# flow3r-pot.net
KiCad netlist of a schematic drawn in EAGLE
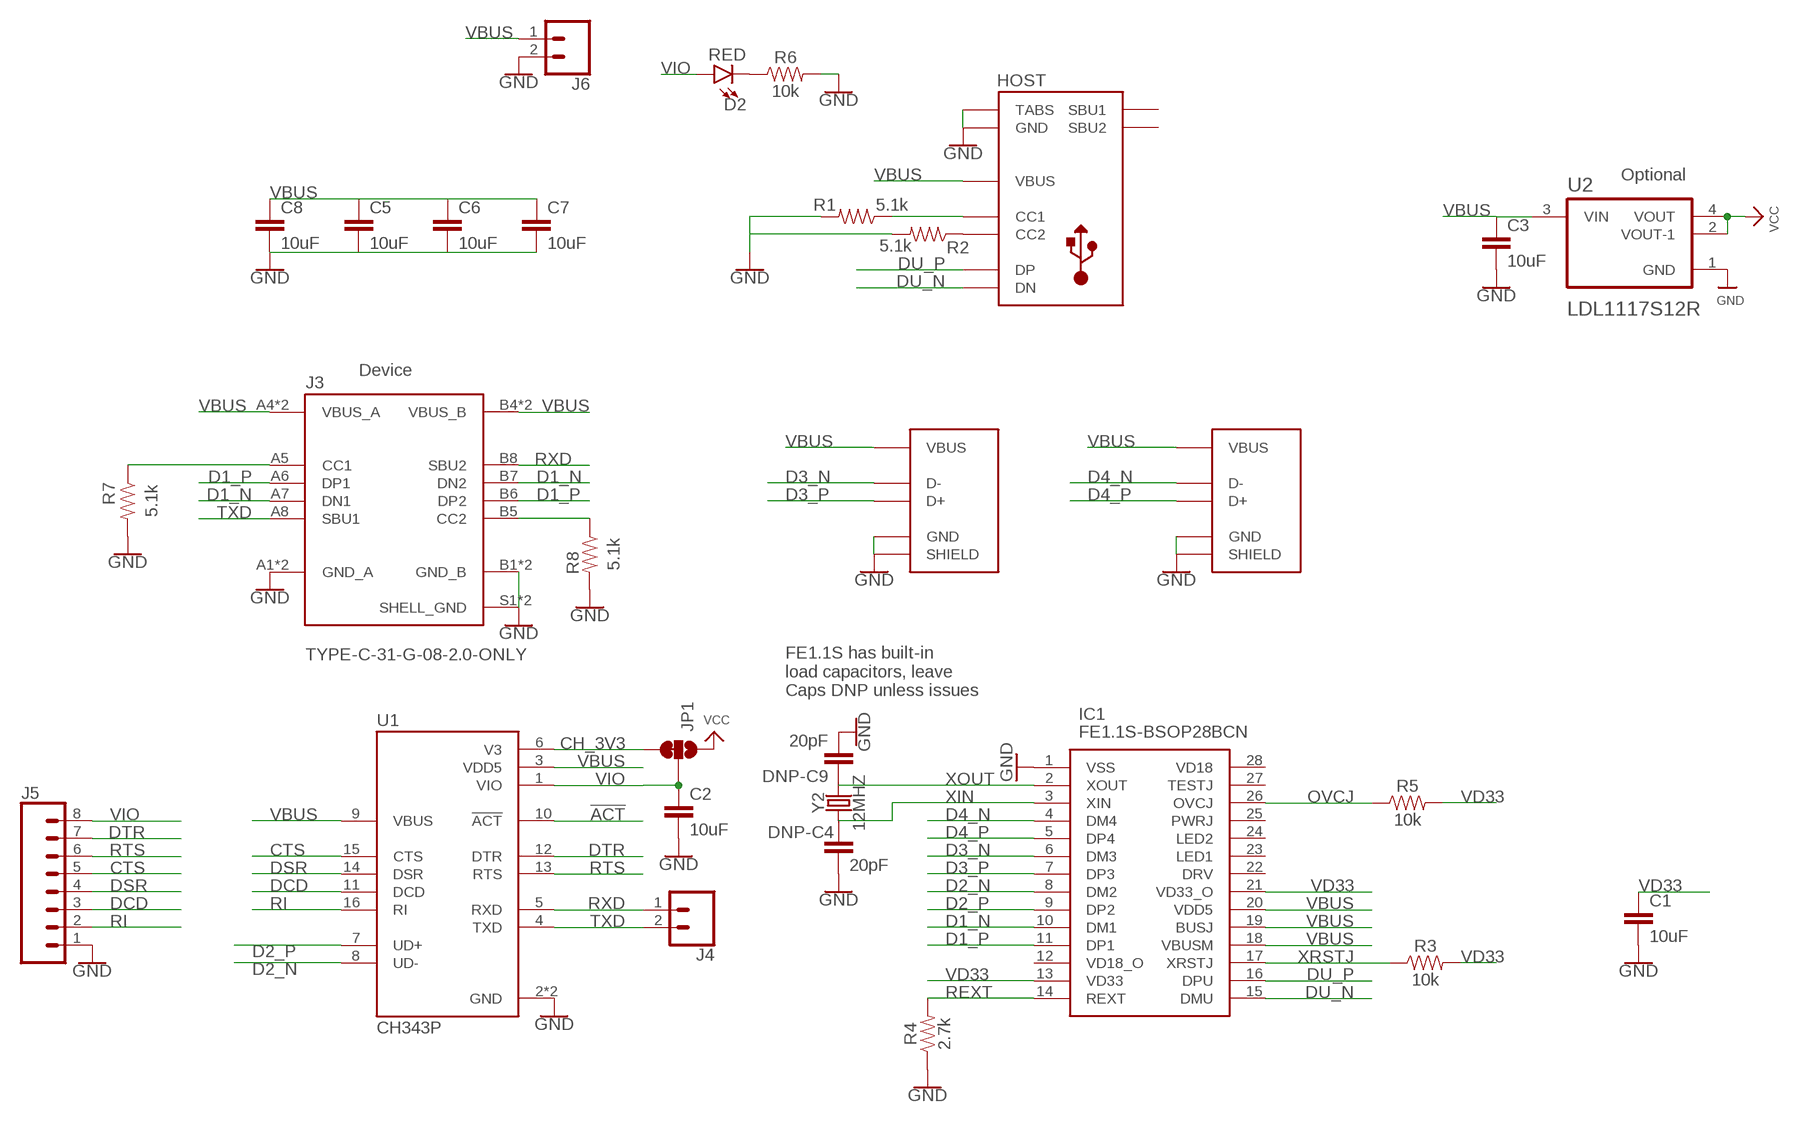
[diagram p0: schematic, sheet 1]

(export (version "E")
  (design (tool "Eeschema 10.0.6"))
  (components
    (comp (ref "C1")
      (value "10uF")
      (footprint "eagle-import:0603")
      (libsource (lib "eagle-import") (part "1.0UF-0603-16V-10%"))
    )
    (comp (ref "C2")
      (value "10uF")
      (footprint "eagle-import:0603")
      (libsource (lib "eagle-import") (part "1.0UF-0603-16V-10%"))
    )
    (comp (ref "C3")
      (value "10uF")
      (footprint "eagle-import:0603")
      (libsource (lib "eagle-import") (part "1.0UF-0603-16V-10%"))
    )
    (comp (ref "C5")
      (value "10uF")
      (footprint "eagle-import:0603")
      (libsource (lib "eagle-import") (part "1.0UF-0603-16V-10%"))
    )
    (comp (ref "C6")
      (value "10uF")
      (footprint "eagle-import:0603")
      (libsource (lib "eagle-import") (part "1.0UF-0603-16V-10%"))
    )
    (comp (ref "C7")
      (value "10uF")
      (footprint "eagle-import:0603")
      (libsource (lib "eagle-import") (part "1.0UF-0603-16V-10%"))
    )
    (comp (ref "C8")
      (value "10uF")
      (footprint "eagle-import:0603")
      (libsource (lib "eagle-import") (part "1.0UF-0603-16V-10%"))
    )
    (comp (ref "D2")
      (value "RED")
      (footprint "eagle-import:LED-0603")
      (libsource (lib "eagle-import") (part "LED-RED0603"))
    )
    (comp (ref "DNP-C4")
      (value "20pF")
      (footprint "eagle-import:0402-TIGHT")
      (libsource (lib "eagle-import") (part "20PF-0402T-50V-5%"))
    )
    (comp (ref "DNP-C9")
      (value "20pF")
      (footprint "eagle-import:0402-TIGHT")
      (libsource (lib "eagle-import") (part "20PF-0402T-50V-5%"))
    )
    (comp (ref "IC1")
      (value "FE1.1S-BSOP28BCN")
      (footprint "eagle-import:SOP64P600X175-28N")
      (libsource (lib "eagle-import") (part "FE1.1S-BSOP28BCN"))
    )
    (comp (ref "J1")
      (value "JE-USB-A-C42595")
      (footprint "eagle-import:JE-USB-A-C42595")
      (libsource (lib "eagle-import") (part "JE-USB-A-C42595"))
    )
    (comp (ref "J2")
      (value "JE-USB-A-C42595")
      (footprint "eagle-import:JE-USB-A-C42595")
      (libsource (lib "eagle-import") (part "JE-USB-A-C42595"))
    )
    (comp (ref "J3")
      (value "TYPE-C-31-G-08-2.0-ONLY")
      (footprint "eagle-import:TYPE-C-31-G-08-2.0-ONLY")
      (fields (field (name "MF") "HRO") (field (name "MP") "TYPE-C-31-G-08"))
      (libsource (lib "eagle-import") (part "TYPE-C-31-G-08-2.0-ONLY"))
    )
    (comp (ref "J4")
      (value "CONN_02")
      (footprint "eagle-import:1X02")
      (libsource (lib "eagle-import") (part "CONN_02"))
    )
    (comp (ref "J5")
      (value "CONN_08LOCK_LONGPADS")
      (footprint "eagle-import:1X08_LOCK_LONGPADS")
      (libsource (lib "eagle-import") (part "CONN_08LOCK_LONGPADS"))
    )
    (comp (ref "J6")
      (value "CONN_02")
      (footprint "eagle-import:1X02")
      (libsource (lib "eagle-import") (part "CONN_02"))
    )
    (comp (ref "JP1")
      (value "JUMPER-SMT_3_1-NC_TRACE_NO-SILK")
      (footprint "eagle-import:SMT-JUMPER_3_1-NC_TRACE_NO-SILK")
      (libsource (lib "eagle-import") (part "JUMPER-SMT_3_1-NC_TRACE_NO-SILK"))
    )
    (comp (ref "R1")
      (value "5.1k")
      (footprint "eagle-import:0603")
      (libsource (lib "eagle-import") (part "5.1KOHM5.1KOHM-0603-1/10W-1%"))
    )
    (comp (ref "R2")
      (value "5.1k")
      (footprint "eagle-import:0603")
      (libsource (lib "eagle-import") (part "5.1KOHM5.1KOHM-0603-1/10W-1%"))
    )
    (comp (ref "R3")
      (value "10k")
      (footprint "eagle-import:0603")
      (libsource (lib "eagle-import") (part "10KOHM-0603-1/10W-1%"))
    )
    (comp (ref "R4")
      (value "2.7k")
      (footprint "eagle-import:0603")
      (libsource (lib "eagle-import") (part "2.7KOHM-0603-1/10W-1%"))
    )
    (comp (ref "R5")
      (value "10k")
      (footprint "eagle-import:0603")
      (libsource (lib "eagle-import") (part "10KOHM-0603-1/10W-1%"))
    )
    (comp (ref "R6")
      (value "10k")
      (footprint "eagle-import:0603")
      (libsource (lib "eagle-import") (part "10KOHM-0603-1/10W-1%"))
    )
    (comp (ref "R7")
      (value "5.1k")
      (footprint "eagle-import:0603")
      (libsource (lib "eagle-import") (part "5.1KOHM5.1KOHM-0603-1/10W-1%"))
    )
    (comp (ref "R8")
      (value "5.1k")
      (footprint "eagle-import:0603")
      (libsource (lib "eagle-import") (part "5.1KOHM5.1KOHM-0603-1/10W-1%"))
    )
    (comp (ref "U1")
      (value "CH343P")
      (footprint "eagle-import:QFN50P300X300X80-17N")
      (fields (field (name "MF") "WCH"))
      (libsource (lib "eagle-import") (part "CH343P"))
    )
    (comp (ref "U2")
      (value "LDL1117S12R")
      (footprint "eagle-import:SOT230P700X180-4N")
      (fields (field (name "MF") "STMicroelectronics"))
      (libsource (lib "eagle-import") (part "LDL1117S12R"))
    )
    (comp (ref "USB-C-HOST")
      (value "C709357")
      (footprint "eagle-import:USB-TYPE-C_16PIN-MALE-TYPE-C-31-M-12")
      (libsource (lib "eagle-import") (part "TYPE-C-31-M-12"))
    )
    (comp (ref "Y2")
      (value "12MHZ")
      (footprint "eagle-import:CRYSTAL-SMD-2X2.5MM")
      (libsource (lib "eagle-import") (part "CRYSTAL-12MHZ"))
    )
  )
  (nets
    (net (code "1") (name "/CH_3V3") (class "Default")
      (node (ref "JP1") (pin "3") (pinfunction "3_3") (pintype "passive"))
      (node (ref "U1") (pin "6") (pinfunction "V3_6") (pintype "power_in"))
    )
    (net (code "2") (name "/CTS") (class "Default")
      (node (ref "J5") (pin "5") (pinfunction "5_5") (pintype "passive"))
      (node (ref "U1") (pin "15") (pinfunction "CTS_15") (pintype "input"))
    )
    (net (code "3") (name "/D1_N") (class "Default")
      (node (ref "IC1") (pin "10") (pinfunction "DM1_10") (pintype "bidirectional"))
      (node (ref "J3") (pin "A7") (pinfunction "DN1_A7") (pintype "bidirectional"))
      (node (ref "J3") (pin "B7") (pinfunction "DN2_B7") (pintype "bidirectional"))
    )
    (net (code "4") (name "/D1_P") (class "Default")
      (node (ref "IC1") (pin "11") (pinfunction "DP1_11") (pintype "bidirectional"))
      (node (ref "J3") (pin "A6") (pinfunction "DP1_A6") (pintype "bidirectional"))
      (node (ref "J3") (pin "B6") (pinfunction "DP2_B6") (pintype "bidirectional"))
    )
    (net (code "5") (name "/D2_N") (class "Default")
      (node (ref "IC1") (pin "8") (pinfunction "DM2_8") (pintype "bidirectional"))
      (node (ref "U1") (pin "8") (pinfunction "UD-_8") (pintype "bidirectional"))
    )
    (net (code "6") (name "/D2_P") (class "Default")
      (node (ref "IC1") (pin "9") (pinfunction "DP2_9") (pintype "bidirectional"))
      (node (ref "U1") (pin "7") (pinfunction "UD+_7") (pintype "bidirectional"))
    )
    (net (code "7") (name "/D3_N") (class "Default")
      (node (ref "IC1") (pin "6") (pinfunction "DM3_6") (pintype "bidirectional"))
      (node (ref "J1") (pin "D-") (pinfunction "D-_D-") (pintype "bidirectional"))
    )
    (net (code "8") (name "/D3_P") (class "Default")
      (node (ref "IC1") (pin "7") (pinfunction "DP3_7") (pintype "bidirectional"))
      (node (ref "J1") (pin "D+") (pinfunction "D+_D+") (pintype "bidirectional"))
    )
    (net (code "9") (name "/D4_N") (class "Default")
      (node (ref "IC1") (pin "4") (pinfunction "DM4_4") (pintype "bidirectional"))
      (node (ref "J2") (pin "D-") (pinfunction "D-_D-") (pintype "bidirectional"))
    )
    (net (code "10") (name "/D4_P") (class "Default")
      (node (ref "IC1") (pin "5") (pinfunction "DP4_5") (pintype "bidirectional"))
      (node (ref "J2") (pin "D+") (pinfunction "D+_D+") (pintype "bidirectional"))
    )
    (net (code "11") (name "/DCD") (class "Default")
      (node (ref "J5") (pin "3") (pinfunction "3_3") (pintype "passive"))
      (node (ref "U1") (pin "11") (pinfunction "DCD_11") (pintype "input"))
    )
    (net (code "12") (name "/DSR") (class "Default")
      (node (ref "J5") (pin "4") (pinfunction "4_4") (pintype "passive"))
      (node (ref "U1") (pin "14") (pinfunction "DSR_14") (pintype "input"))
    )
    (net (code "13") (name "/DTR") (class "Default")
      (node (ref "J5") (pin "7") (pinfunction "7_7") (pintype "passive"))
      (node (ref "U1") (pin "12") (pinfunction "DTR_12") (pintype "output"))
    )
    (net (code "14") (name "/DU_N") (class "Default")
      (node (ref "IC1") (pin "15") (pinfunction "DMU_15") (pintype "bidirectional"))
      (node (ref "USB-C-HOST") (pin "A7") (pinfunction "DN_A7") (pintype "bidirectional"))
      (node (ref "USB-C-HOST") (pin "B7") (pinfunction "DN_B7") (pintype "bidirectional"))
    )
    (net (code "15") (name "/DU_P") (class "Default")
      (node (ref "IC1") (pin "16") (pinfunction "DPU_16") (pintype "bidirectional"))
      (node (ref "USB-C-HOST") (pin "A6") (pinfunction "DP_A6") (pintype "bidirectional"))
      (node (ref "USB-C-HOST") (pin "B6") (pinfunction "DP_B6") (pintype "bidirectional"))
    )
    (net (code "16") (name "/OVCJ") (class "Default")
      (node (ref "IC1") (pin "26") (pinfunction "OVCJ_26") (pintype "bidirectional"))
      (node (ref "R5") (pin "1") (pinfunction "1_1") (pintype "passive"))
    )
    (net (code "17") (name "/REXT") (class "Default")
      (node (ref "IC1") (pin "14") (pinfunction "REXT_14") (pintype "bidirectional"))
      (node (ref "R4") (pin "2") (pinfunction "2_2") (pintype "passive"))
    )
    (net (code "18") (name "/RI") (class "Default")
      (node (ref "J5") (pin "2") (pinfunction "2_2") (pintype "passive"))
      (node (ref "U1") (pin "16") (pinfunction "RI_16") (pintype "input"))
    )
    (net (code "19") (name "/RTS") (class "Default")
      (node (ref "J5") (pin "6") (pinfunction "6_6") (pintype "passive"))
      (node (ref "U1") (pin "13") (pinfunction "RTS_13") (pintype "output"))
    )
    (net (code "20") (name "/RXD") (class "Default")
      (node (ref "J3") (pin "B8") (pinfunction "SBU2_B8") (pintype "bidirectional"))
      (node (ref "J4") (pin "1") (pinfunction "1_1") (pintype "passive"))
      (node (ref "U1") (pin "5") (pinfunction "RXD_5") (pintype "input"))
    )
    (net (code "21") (name "/TXD") (class "Default")
      (node (ref "J3") (pin "A8") (pinfunction "SBU1_A8") (pintype "bidirectional"))
      (node (ref "J4") (pin "2") (pinfunction "2_2") (pintype "passive"))
      (node (ref "U1") (pin "4") (pinfunction "TXD_4") (pintype "output"))
    )
    (net (code "22") (name "/VBUS") (class "Default")
      (node (ref "C3") (pin "1") (pinfunction "1_1") (pintype "passive"))
      (node (ref "C5") (pin "1") (pinfunction "1_1") (pintype "passive"))
      (node (ref "C6") (pin "1") (pinfunction "1_1") (pintype "passive"))
      (node (ref "C7") (pin "1") (pinfunction "1_1") (pintype "passive"))
      (node (ref "C8") (pin "1") (pinfunction "1_1") (pintype "passive"))
      (node (ref "IC1") (pin "18") (pinfunction "VBUSM_18") (pintype "bidirectional"))
      (node (ref "IC1") (pin "19") (pinfunction "BUSJ_19") (pintype "bidirectional"))
      (node (ref "IC1") (pin "20") (pinfunction "VDD5_20") (pintype "bidirectional"))
      (node (ref "J1") (pin "VBUS") (pinfunction "VBUS_VBUS") (pintype "power_in"))
      (node (ref "J2") (pin "VBUS") (pinfunction "VBUS_VBUS") (pintype "power_in"))
      (node (ref "J3") (pin "A4") (pinfunction "VBUS_A_A4") (pintype "power_in"))
      (node (ref "J3") (pin "A9") (pinfunction "VBUS_A_A9") (pintype "power_in"))
      (node (ref "J3") (pin "B4") (pinfunction "VBUS_B_B4") (pintype "power_in"))
      (node (ref "J3") (pin "B9") (pinfunction "VBUS_B_B9") (pintype "power_in"))
      (node (ref "J6") (pin "1") (pinfunction "1_1") (pintype "passive"))
      (node (ref "U1") (pin "3") (pinfunction "VDD5_3") (pintype "power_in"))
      (node (ref "U1") (pin "9") (pinfunction "VBUS_9") (pintype "input"))
      (node (ref "U2") (pin "3") (pinfunction "VIN_3") (pintype "input"))
      (node (ref "USB-C-HOST") (pin "A4") (pinfunction "VBUS_A4") (pintype "bidirectional"))
      (node (ref "USB-C-HOST") (pin "A9") (pinfunction "VBUS_A9") (pintype "bidirectional"))
      (node (ref "USB-C-HOST") (pin "B4") (pinfunction "VBUS_B4") (pintype "bidirectional"))
      (node (ref "USB-C-HOST") (pin "B9") (pinfunction "VBUS_B9") (pintype "bidirectional"))
    )
    (net (code "23") (name "/VD33") (class "Default")
      (node (ref "C1") (pin "1") (pinfunction "1_1") (pintype "passive"))
      (node (ref "IC1") (pin "13") (pinfunction "VD33_13") (pintype "bidirectional"))
      (node (ref "IC1") (pin "21") (pinfunction "VD33_O_21") (pintype "bidirectional"))
      (node (ref "R3") (pin "2") (pinfunction "2_2") (pintype "passive"))
      (node (ref "R5") (pin "2") (pinfunction "2_2") (pintype "passive"))
    )
    (net (code "24") (name "/VIO") (class "Default")
      (node (ref "C2") (pin "1") (pinfunction "1_1") (pintype "passive"))
      (node (ref "D2") (pin "A") (pinfunction "A_A") (pintype "passive"))
      (node (ref "J5") (pin "8") (pinfunction "8_8") (pintype "passive"))
      (node (ref "JP1") (pin "2") (pinfunction "2_2") (pintype "passive"))
      (node (ref "U1") (pin "1") (pinfunction "VIO_1") (pintype "power_in"))
    )
    (net (code "25") (name "/XIN") (class "Default")
      (node (ref "DNP-C4") (pin "1") (pinfunction "1_1") (pintype "passive"))
      (node (ref "IC1") (pin "3") (pinfunction "XIN_3") (pintype "bidirectional"))
      (node (ref "Y2") (pin "P1") (pinfunction "1_P1") (pintype "passive"))
    )
    (net (code "26") (name "/XOUT") (class "Default")
      (node (ref "DNP-C9") (pin "1") (pinfunction "1_1") (pintype "passive"))
      (node (ref "IC1") (pin "2") (pinfunction "XOUT_2") (pintype "bidirectional"))
      (node (ref "Y2") (pin "P3") (pinfunction "2_P3") (pintype "passive"))
    )
    (net (code "27") (name "/XRSTJ") (class "Default")
      (node (ref "IC1") (pin "17") (pinfunction "XRSTJ_17") (pintype "bidirectional"))
      (node (ref "R3") (pin "1") (pinfunction "1_1") (pintype "passive"))
    )
    (net (code "28") (name "/~{ACT}") (class "Default")
      (node (ref "U1") (pin "10") (pinfunction "~{ACT}_10") (pintype "output"))
    )
    (net (code "29") (name "GND") (class "Default")
      (node (ref "C1") (pin "2") (pinfunction "2_2") (pintype "passive"))
      (node (ref "C2") (pin "2") (pinfunction "2_2") (pintype "passive"))
      (node (ref "C3") (pin "2") (pinfunction "2_2") (pintype "passive"))
      (node (ref "C5") (pin "2") (pinfunction "2_2") (pintype "passive"))
      (node (ref "C6") (pin "2") (pinfunction "2_2") (pintype "passive"))
      (node (ref "C7") (pin "2") (pinfunction "2_2") (pintype "passive"))
      (node (ref "C8") (pin "2") (pinfunction "2_2") (pintype "passive"))
      (node (ref "DNP-C4") (pin "2") (pinfunction "2_2") (pintype "passive"))
      (node (ref "DNP-C9") (pin "2") (pinfunction "2_2") (pintype "passive"))
      (node (ref "IC1") (pin "1") (pinfunction "VSS_1") (pintype "bidirectional"))
      (node (ref "J1") (pin "GND") (pinfunction "GND_GND") (pintype "bidirectional"))
      (node (ref "J1") (pin "SHIELD-1") (pinfunction "SHIELD_SHIELD-1") (pintype "bidirectional"))
      (node (ref "J1") (pin "SHIELD-2") (pinfunction "SHIELD_SHIELD-2") (pintype "bidirectional"))
      (node (ref "J2") (pin "GND") (pinfunction "GND_GND") (pintype "bidirectional"))
      (node (ref "J2") (pin "SHIELD-1") (pinfunction "SHIELD_SHIELD-1") (pintype "bidirectional"))
      (node (ref "J2") (pin "SHIELD-2") (pinfunction "SHIELD_SHIELD-2") (pintype "bidirectional"))
      (node (ref "J3") (pin "A1") (pinfunction "GND_A_A1") (pintype "power_in"))
      (node (ref "J3") (pin "A12") (pinfunction "GND_A_A12") (pintype "power_in"))
      (node (ref "J3") (pin "B1") (pinfunction "GND_B_B1") (pintype "power_in"))
      (node (ref "J3") (pin "B12") (pinfunction "GND_B_B12") (pintype "power_in"))
      (node (ref "J3") (pin "S1") (pinfunction "SHELL_GND_S1") (pintype "power_in"))
      (node (ref "J3") (pin "S2") (pinfunction "SHELL_GND_S2") (pintype "power_in"))
      (node (ref "J5") (pin "1") (pinfunction "1_1") (pintype "passive"))
      (node (ref "J6") (pin "2") (pinfunction "2_2") (pintype "passive"))
      (node (ref "R1") (pin "2") (pinfunction "2_2") (pintype "passive"))
      (node (ref "R2") (pin "2") (pinfunction "2_2") (pintype "passive"))
      (node (ref "R4") (pin "1") (pinfunction "1_1") (pintype "passive"))
      (node (ref "R6") (pin "2") (pinfunction "2_2") (pintype "passive"))
      (node (ref "R7") (pin "2") (pinfunction "2_2") (pintype "passive"))
      (node (ref "R8") (pin "2") (pinfunction "2_2") (pintype "passive"))
      (node (ref "U1") (pin "17") (pinfunction "GND_17") (pintype "power_in"))
      (node (ref "U1") (pin "2") (pinfunction "GND_2") (pintype "power_in"))
      (node (ref "U2") (pin "1") (pinfunction "GND_1") (pintype "power_in"))
      (node (ref "USB-C-HOST") (pin "0") (pinfunction "TABS_0") (pintype "bidirectional"))
      (node (ref "USB-C-HOST") (pin "0-1") (pinfunction "TABS_0-1") (pintype "bidirectional"))
      (node (ref "USB-C-HOST") (pin "0-2") (pinfunction "TABS_0-2") (pintype "bidirectional"))
      (node (ref "USB-C-HOST") (pin "0-3") (pinfunction "TABS_0-3") (pintype "bidirectional"))
      (node (ref "USB-C-HOST") (pin "A1") (pinfunction "GND_A1") (pintype "bidirectional"))
      (node (ref "USB-C-HOST") (pin "A12") (pinfunction "GND_A12") (pintype "bidirectional"))
      (node (ref "USB-C-HOST") (pin "B1") (pinfunction "GND_B1") (pintype "bidirectional"))
      (node (ref "USB-C-HOST") (pin "B12") (pinfunction "GND_B12") (pintype "bidirectional"))
    )
    (net (code "30") (name "Net-(D2-PadC)") (class "Default")
      (node (ref "D2") (pin "C") (pinfunction "C_C") (pintype "passive"))
      (node (ref "R6") (pin "1") (pinfunction "1_1") (pintype "passive"))
    )
    (net (code "31") (name "Net-(J3-CC1)") (class "Default")
      (node (ref "J3") (pin "A5") (pinfunction "CC1_A5") (pintype "bidirectional"))
      (node (ref "R7") (pin "1") (pinfunction "1_1") (pintype "passive"))
    )
    (net (code "32") (name "Net-(J3-CC2)") (class "Default")
      (node (ref "J3") (pin "B5") (pinfunction "CC2_B5") (pintype "bidirectional"))
      (node (ref "R8") (pin "1") (pinfunction "1_1") (pintype "passive"))
    )
    (net (code "33") (name "Net-(USB-C-HOST-CC1)") (class "Default")
      (node (ref "R1") (pin "1") (pinfunction "1_1") (pintype "passive"))
      (node (ref "USB-C-HOST") (pin "A5") (pinfunction "CC1_A5") (pintype "bidirectional"))
    )
    (net (code "34") (name "Net-(USB-C-HOST-CC2)") (class "Default")
      (node (ref "R2") (pin "1") (pinfunction "1_1") (pintype "passive"))
      (node (ref "USB-C-HOST") (pin "B5") (pinfunction "CC2_B5") (pintype "bidirectional"))
    )
    (net (code "35") (name "VCC") (class "Default")
      (node (ref "JP1") (pin "1") (pinfunction "1_1") (pintype "passive"))
      (node (ref "U2") (pin "2") (pinfunction "VOUT-1_2") (pintype "output"))
      (node (ref "U2") (pin "4") (pinfunction "VOUT_4") (pintype "output"))
    )
    (net (code "36") (name "unconnected-(IC1-DRV-Pad22)") (class "Default")
      (node (ref "IC1") (pin "22") (pinfunction "DRV_22") (pintype "bidirectional"))
    )
    (net (code "37") (name "unconnected-(IC1-LED1-Pad23)") (class "Default")
      (node (ref "IC1") (pin "23") (pinfunction "LED1_23") (pintype "bidirectional"))
    )
    (net (code "38") (name "unconnected-(IC1-LED2-Pad24)") (class "Default")
      (node (ref "IC1") (pin "24") (pinfunction "LED2_24") (pintype "bidirectional"))
    )
    (net (code "39") (name "unconnected-(IC1-PWRJ-Pad25)") (class "Default")
      (node (ref "IC1") (pin "25") (pinfunction "PWRJ_25") (pintype "bidirectional"))
    )
    (net (code "40") (name "unconnected-(IC1-TESTJ-Pad27)") (class "Default")
      (node (ref "IC1") (pin "27") (pinfunction "TESTJ_27") (pintype "bidirectional"))
    )
    (net (code "41") (name "unconnected-(IC1-VD18-Pad28)") (class "Default")
      (node (ref "IC1") (pin "28") (pinfunction "VD18_28") (pintype "bidirectional"))
    )
    (net (code "42") (name "unconnected-(IC1-VD18_O-Pad12)") (class "Default")
      (node (ref "IC1") (pin "12") (pinfunction "VD18_O_12") (pintype "bidirectional"))
    )
    (net (code "43") (name "unconnected-(USB-C-HOST-SBU1-PadA8)") (class "Default")
      (node (ref "USB-C-HOST") (pin "A8") (pinfunction "SBU1_A8") (pintype "bidirectional"))
    )
    (net (code "44") (name "unconnected-(USB-C-HOST-SBU2-PadB8)") (class "Default")
      (node (ref "USB-C-HOST") (pin "B8") (pinfunction "SBU2_B8") (pintype "bidirectional"))
    )
  )
)
